# Sheet1.net
KiCad netlist of a schematic drawn in Altium Designer
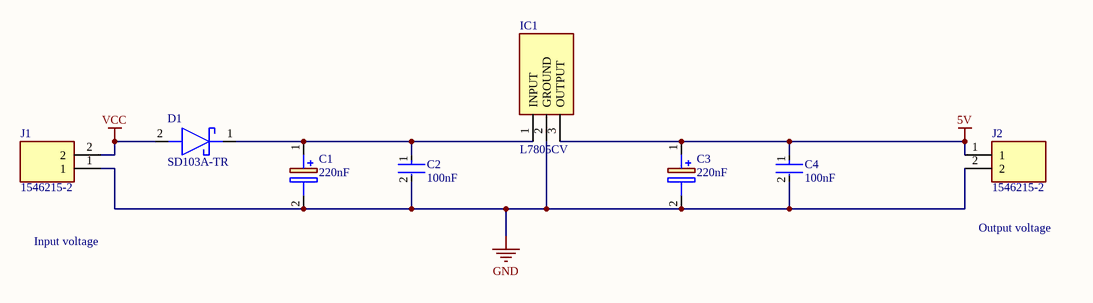
[diagram p0: Sheet1.SchDoc]

(export (version "E")
  (design (tool "Eeschema 10.0.6"))
  (components
    (comp (ref "C1")
      (value "220nF")
      (footprint "SamacSys:CAPPRD200W55D500H1250")
      (description "Capacitor Polarised")
      (fields
        (field (name "MANUFACTURER_PART_NUMBER") "EEU-FR1H100")
        (field (name "MOUSER PART NUMBER") "667-EEU-FR1H100")
      )
      (libsource (lib "*") (part "EEU-FR1H100"))
    )
    (comp (ref "C2")
      (value "100nF")
      (footprint "FP-RDE0P1-MFG")
      (description "Ceramic Capacitor 100nF ±10% 25V X7R Radial")
      (fields (field (name "TOLERANCE") "10%"))
      (libsource (lib "Altium Content Vault") (part "b4654b650e69147ec39a6b967a45e02"))
    )
    (comp (ref "C3")
      (value "220nF")
      (footprint "SamacSys:CAPPRD200W55D500H1250")
      (description "Capacitor Polarised")
      (fields
        (field (name "MANUFACTURER_PART_NUMBER") "EEU-FR1H100")
        (field (name "MOUSER PART NUMBER") "667-EEU-FR1H100")
      )
      (libsource (lib "*") (part "EEU-FR1H100"))
    )
    (comp (ref "C4")
      (value "100nF")
      (footprint "FP-RDE0P1-MFG")
      (description "Ceramic Capacitor 100nF ±10% 25V X7R Radial")
      (fields (field (name "TOLERANCE") "10%"))
      (libsource (lib "Altium Content Vault") (part "b4654b650e69147ec39a6b967a45e02"))
    )
    (comp (ref "D1")
      (value "SD103A-TR")
      (footprint "SamacSys:DIOAD950W60L350D150")
      (description "Schottky Diode")
      (fields (field (name "MOUSER PART NUMBER") "625-SD103A"))
      (libsource (lib "*") (part "SD103A-TR"))
    )
    (comp (ref "IC1")
      (value "L7805CV")
      (footprint "SamacSys:TO255P460X1020X2008-3P")
      (description "Integrated Circuit")
      (fields (field (name "MOUSER PART NUMBER") "511-L7805CV"))
      (libsource (lib "*") (part "L7805CV"))
    )
    (comp (ref "J1")
      (value "1546215-2")
      (footprint "SamacSys:15462152")
      (description "Connector")
      (fields (field (name "MOUSER PART NUMBER") "571-1546215-2"))
      (libsource (lib "") (part "1546215-2_1"))
    )
    (comp (ref "J2")
      (value "1546215-2")
      (footprint "SamacSys:15462152")
      (description "Connector")
      (fields (field (name "MOUSER PART NUMBER") "571-1546215-2"))
      (libsource (lib "*") (part "1546215-2"))
    )
  )
  (nets
    (net (code "1") (name "5V") (class "Default")
      (node (ref "C3") (pin "1") (pinfunction "+_1") (pintype "power_in"))
      (node (ref "C4") (pin "1") (pinfunction "1_1") (pintype "passive"))
      (node (ref "IC1") (pin "3") (pinfunction "OUTPUT_3") (pintype "passive"))
      (node (ref "J2") (pin "1") (pinfunction "1_1") (pintype "passive"))
    )
    (net (code "2") (name "GND") (class "Default")
      (node (ref "C1") (pin "2") (pinfunction "-_2") (pintype "power_in"))
      (node (ref "C2") (pin "2") (pinfunction "2_2") (pintype "passive"))
      (node (ref "C3") (pin "2") (pinfunction "-_2") (pintype "power_in"))
      (node (ref "C4") (pin "2") (pinfunction "2_2") (pintype "passive"))
      (node (ref "IC1") (pin "2") (pinfunction "GROUND_2") (pintype "passive"))
      (node (ref "J1") (pin "1") (pinfunction "1_1") (pintype "passive"))
      (node (ref "J2") (pin "2") (pinfunction "2_2") (pintype "passive"))
    )
    (net (code "3") (name "Net-(C1-+)") (class "Default")
      (node (ref "C1") (pin "1") (pinfunction "+_1") (pintype "power_in"))
      (node (ref "C2") (pin "1") (pinfunction "1_1") (pintype "passive"))
      (node (ref "D1") (pin "1") (pinfunction "K_1") (pintype "passive"))
      (node (ref "IC1") (pin "1") (pinfunction "INPUT_1") (pintype "passive"))
    )
    (net (code "4") (name "VCC") (class "Default")
      (node (ref "D1") (pin "2") (pinfunction "A_2") (pintype "passive"))
      (node (ref "J1") (pin "2") (pinfunction "2_2") (pintype "passive"))
    )
  )
)
